# SmartON.net
KiCad netlist of a schematic drawn in EAGLE
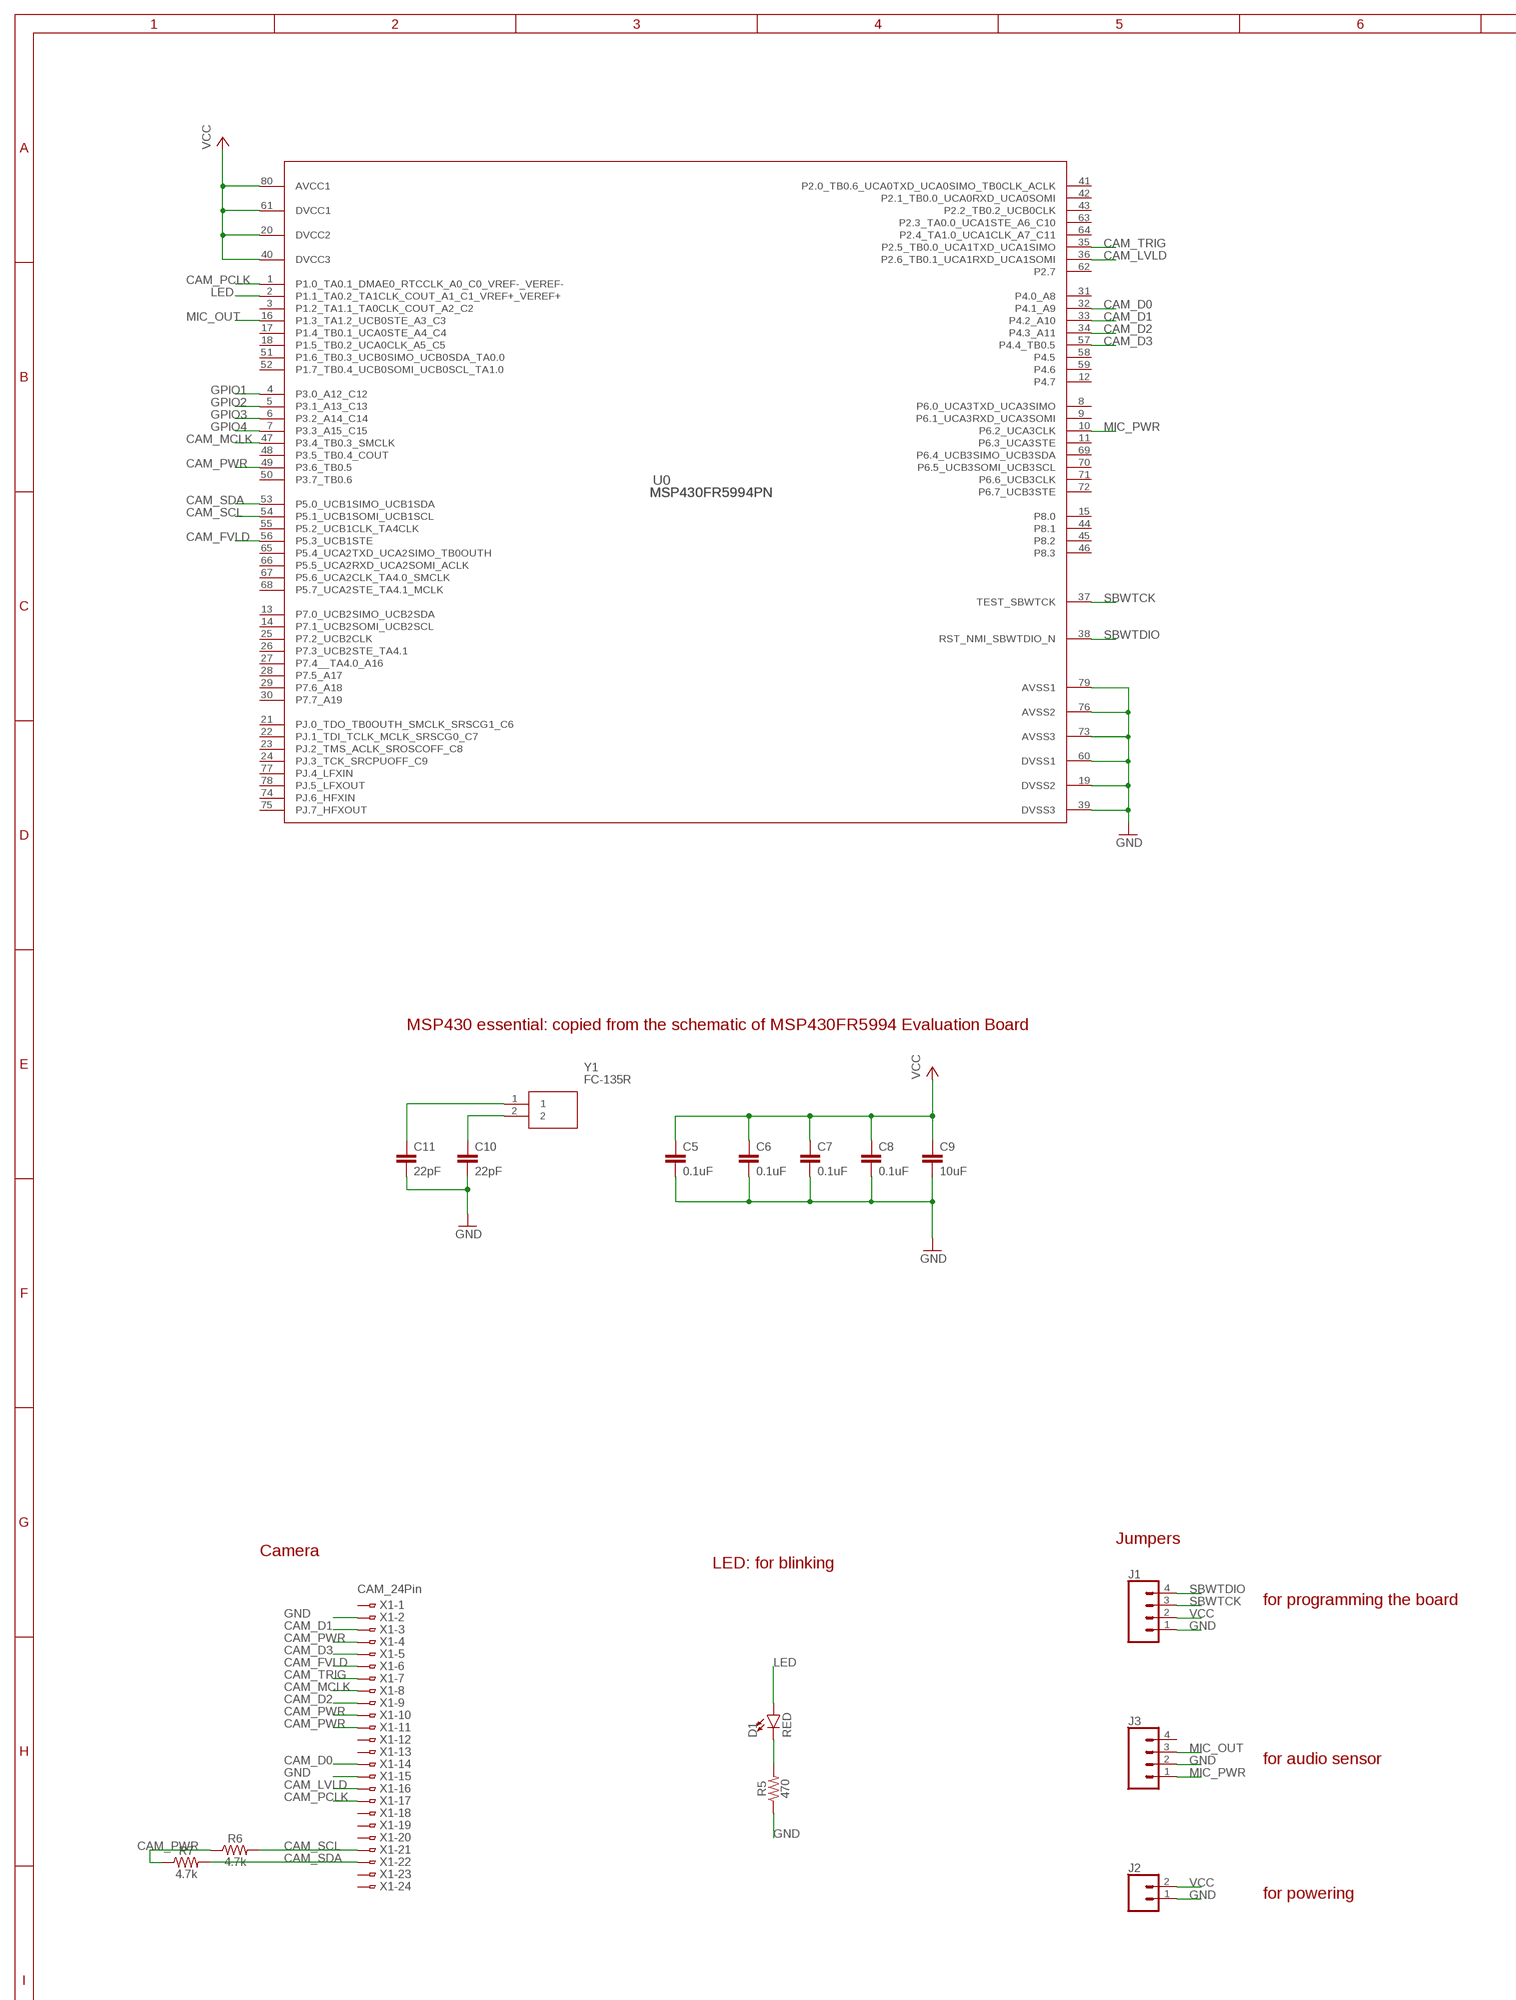
[diagram p0: schematic, sheet 1, part 1 of 2]
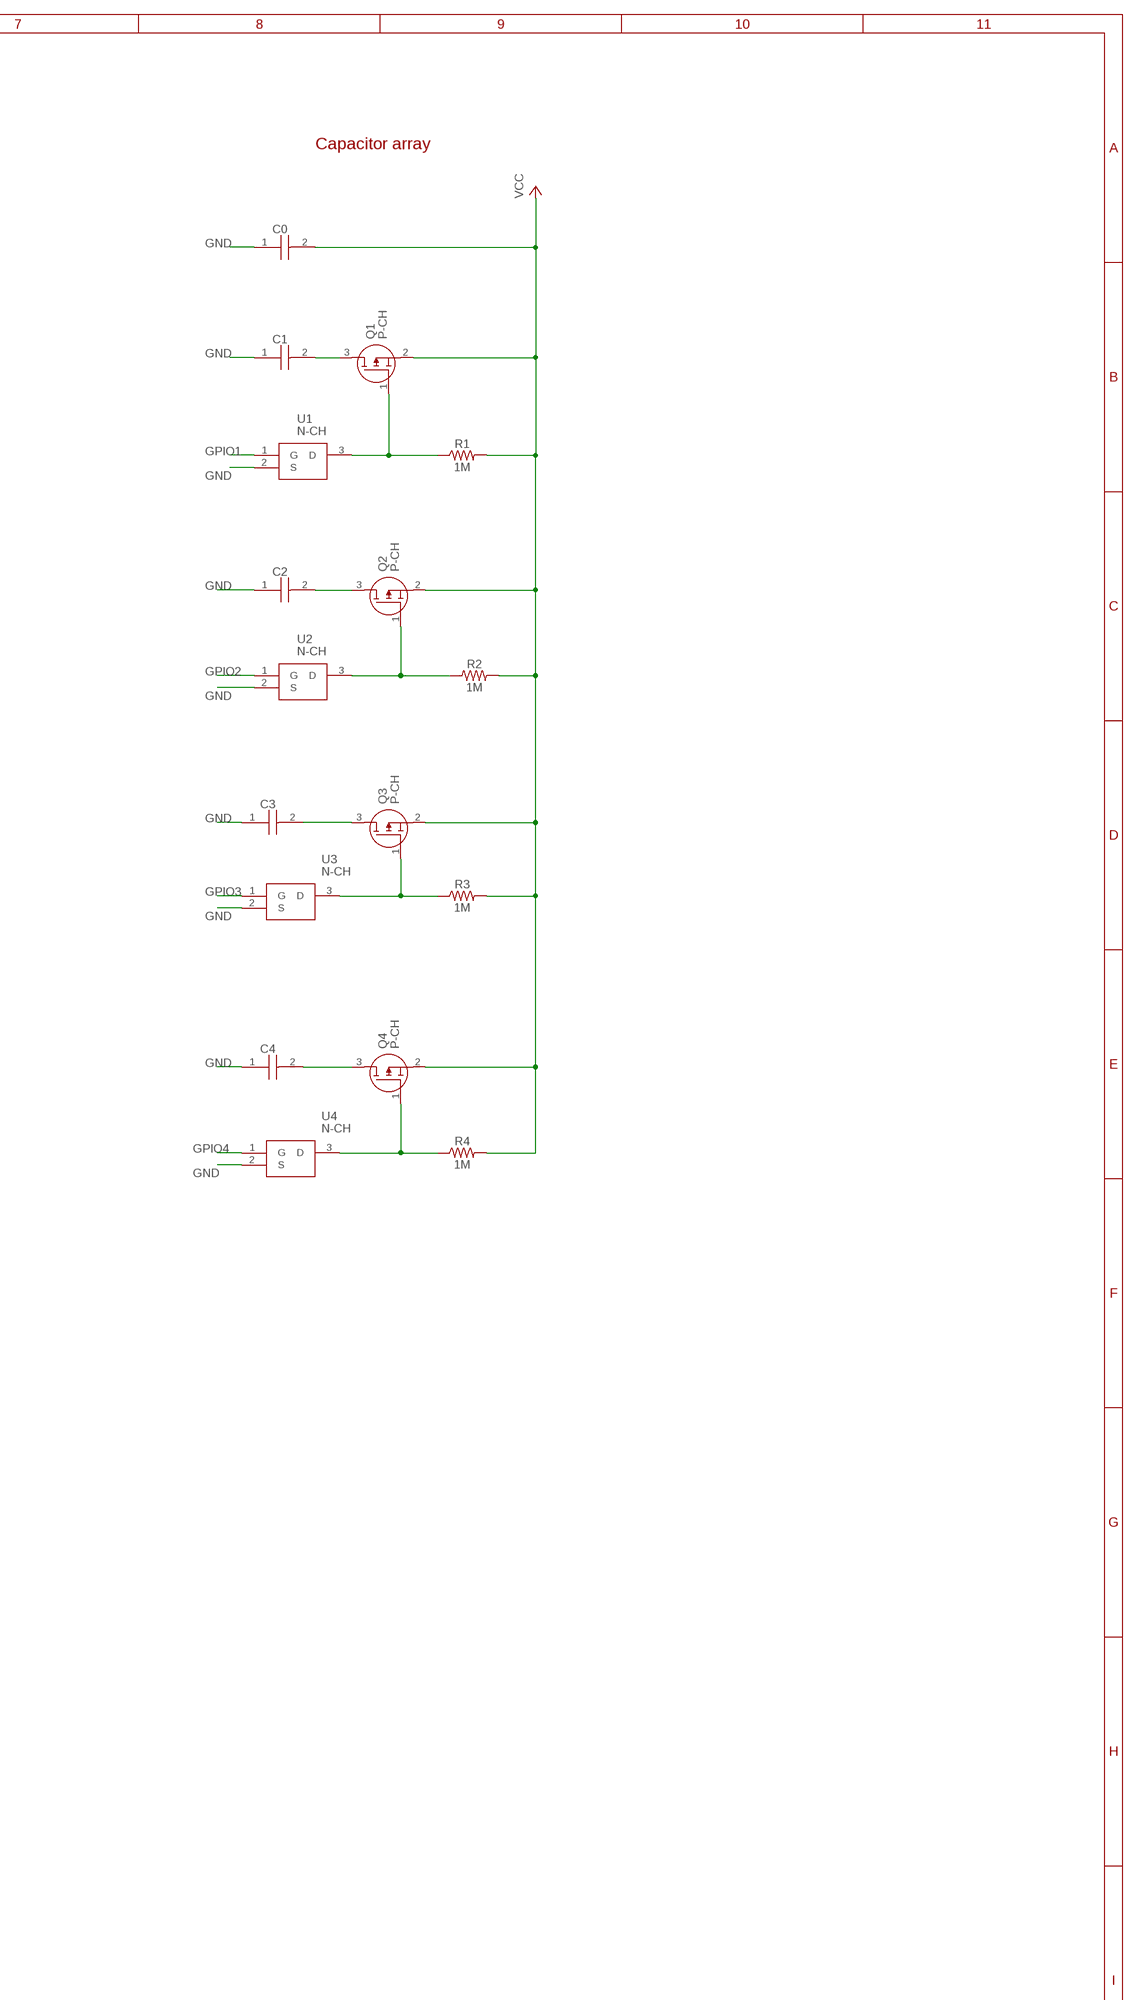
[diagram p1: schematic, sheet 1, part 2 of 2]

(export (version "E")
  (design (tool "Eeschema 10.0.6"))
  (components
    (comp (ref "C0")
      (value "DBN-5R5D224T")
      (footprint "eagle-import:CAPPRD500W130D1350H800")
      (libsource (lib "eagle-import") (part "DBN-5R5D224T"))
    )
    (comp (ref "C1")
      (value "DBN-5R5D224T")
      (footprint "eagle-import:CAPPRD500W130D1350H800")
      (libsource (lib "eagle-import") (part "DBN-5R5D224T"))
    )
    (comp (ref "C2")
      (value "DBN-5R5D224T")
      (footprint "eagle-import:CAPPRD500W130D1350H800")
      (libsource (lib "eagle-import") (part "DBN-5R5D224T"))
    )
    (comp (ref "C3")
      (value "DBN-5R5D224T")
      (footprint "eagle-import:CAPPRD500W130D1350H800")
      (libsource (lib "eagle-import") (part "DBN-5R5D224T"))
    )
    (comp (ref "C4")
      (value "DBN-5R5D224T")
      (footprint "eagle-import:CAPPRD500W130D1350H800")
      (libsource (lib "eagle-import") (part "DBN-5R5D224T"))
    )
    (comp (ref "C5")
      (value "0.1uF")
      (footprint "eagle-import:0603")
      (libsource (lib "eagle-import") (part "0.1UF-0603-25V-5%"))
    )
    (comp (ref "C6")
      (value "0.1uF")
      (footprint "eagle-import:0603")
      (libsource (lib "eagle-import") (part "0.1UF-0603-25V-5%"))
    )
    (comp (ref "C7")
      (value "0.1uF")
      (footprint "eagle-import:0603")
      (libsource (lib "eagle-import") (part "0.1UF-0603-25V-5%"))
    )
    (comp (ref "C8")
      (value "0.1uF")
      (footprint "eagle-import:0603")
      (libsource (lib "eagle-import") (part "0.1UF-0603-25V-5%"))
    )
    (comp (ref "C9")
      (value "10uF")
      (footprint "eagle-import:0603")
      (libsource (lib "eagle-import") (part "10UF-0603-6.3V-20%"))
    )
    (comp (ref "C10")
      (value "22pF")
      (footprint "eagle-import:0603")
      (libsource (lib "eagle-import") (part "22PF-0603-50V-5%"))
    )
    (comp (ref "C11")
      (value "22pF")
      (footprint "eagle-import:0603")
      (libsource (lib "eagle-import") (part "22PF-0603-50V-5%"))
    )
    (comp (ref "D1")
      (value "RED")
      (footprint "eagle-import:LED-0603")
      (libsource (lib "eagle-import") (part "LED-RED0603"))
    )
    (comp (ref "J1")
      (value "CONN_04LOCK")
      (footprint "eagle-import:1X04_LOCK")
      (libsource (lib "eagle-import") (part "CONN_04LOCK"))
    )
    (comp (ref "J2")
      (value "CONN_02")
      (footprint "eagle-import:1X02")
      (libsource (lib "eagle-import") (part "CONN_02"))
    )
    (comp (ref "J3")
      (value "CONN_04LOCK")
      (footprint "eagle-import:1X04_LOCK")
      (libsource (lib "eagle-import") (part "CONN_04LOCK"))
    )
    (comp (ref "Q1")
      (value "P-CH")
      (footprint "eagle-import:SOT95P237X112-3N")
      (fields (field (name "MANUFACTURER_PART_NUMBER") "IRLML5103PBF"))
      (libsource (lib "eagle-import") (part "IRLML5103PBF"))
    )
    (comp (ref "Q2")
      (value "P-CH")
      (footprint "eagle-import:SOT95P237X112-3N")
      (fields (field (name "MANUFACTURER_PART_NUMBER") "IRLML5103PBF"))
      (libsource (lib "eagle-import") (part "IRLML5103PBF"))
    )
    (comp (ref "Q3")
      (value "P-CH")
      (footprint "eagle-import:SOT95P237X112-3N")
      (fields (field (name "MANUFACTURER_PART_NUMBER") "IRLML5103PBF"))
      (libsource (lib "eagle-import") (part "IRLML5103PBF"))
    )
    (comp (ref "Q4")
      (value "P-CH")
      (footprint "eagle-import:SOT95P237X112-3N")
      (fields (field (name "MANUFACTURER_PART_NUMBER") "IRLML5103PBF"))
      (libsource (lib "eagle-import") (part "IRLML5103PBF"))
    )
    (comp (ref "R1")
      (value "1M")
      (footprint "eagle-import:0603")
      (libsource (lib "eagle-import") (part "1MOHM-0603-1/4W-5%"))
    )
    (comp (ref "R2")
      (value "1M")
      (footprint "eagle-import:0603")
      (libsource (lib "eagle-import") (part "1MOHM-0603-1/4W-5%"))
    )
    (comp (ref "R3")
      (value "1M")
      (footprint "eagle-import:0603")
      (libsource (lib "eagle-import") (part "1MOHM-0603-1/4W-5%"))
    )
    (comp (ref "R4")
      (value "1M")
      (footprint "eagle-import:0603")
      (libsource (lib "eagle-import") (part "1MOHM-0603-1/4W-5%"))
    )
    (comp (ref "R5")
      (value "470")
      (footprint "eagle-import:0603")
      (libsource (lib "eagle-import") (part "470OHM-0603-1/10W-1%"))
    )
    (comp (ref "R6")
      (value "4.7k")
      (footprint "eagle-import:0603")
      (libsource (lib "eagle-import") (part "4.7KOHM-0603-1/10W-1%"))
    )
    (comp (ref "R7")
      (value "4.7k")
      (footprint "eagle-import:0603")
      (libsource (lib "eagle-import") (part "4.7KOHM-0603-1/10W-1%"))
    )
    (comp (ref "U0")
      (value "MSP430FR5994PN")
      (footprint "eagle-import:PN0080A_N")
      (fields
        (field (name "MANUFACTURER") "Texas Instruments")
        (field (name "PARTNUMBER") "MSP430FR5994IPNR")
      )
      (libsource (lib "eagle-import") (part "MSP430FR5994IPN"))
    )
    (comp (ref "U1")
      (value "N-CH")
      (footprint "eagle-import:SOT95P240X110-3N")
      (fields
        (field (name "MANUFACTURER_PART_NUMBER") "DMN2004K-7")
        (field (name "MOUSER_PART_NUMBER") "621-DMN2004K-7")
        (field (name "RS_PART_NUMBER") "7082425P")
      )
      (libsource (lib "eagle-import") (part "DMN2004K-7"))
    )
    (comp (ref "U2")
      (value "N-CH")
      (footprint "eagle-import:SOT95P240X110-3N")
      (fields
        (field (name "MANUFACTURER_PART_NUMBER") "DMN2004K-7")
        (field (name "MOUSER_PART_NUMBER") "621-DMN2004K-7")
        (field (name "RS_PART_NUMBER") "7082425P")
      )
      (libsource (lib "eagle-import") (part "DMN2004K-7"))
    )
    (comp (ref "U3")
      (value "N-CH")
      (footprint "eagle-import:SOT95P240X110-3N")
      (fields
        (field (name "MANUFACTURER_PART_NUMBER") "DMN2004K-7")
        (field (name "MOUSER_PART_NUMBER") "621-DMN2004K-7")
        (field (name "RS_PART_NUMBER") "7082425P")
      )
      (libsource (lib "eagle-import") (part "DMN2004K-7"))
    )
    (comp (ref "U4")
      (value "N-CH")
      (footprint "eagle-import:SOT95P240X110-3N")
      (fields
        (field (name "MANUFACTURER_PART_NUMBER") "DMN2004K-7")
        (field (name "MOUSER_PART_NUMBER") "621-DMN2004K-7")
        (field (name "RS_PART_NUMBER") "7082425P")
      )
      (libsource (lib "eagle-import") (part "DMN2004K-7"))
    )
    (comp (ref "X1")
      (value "CAM_24Pin")
      (footprint "eagle-import:FH12-24S-0.5SH")
      (fields (field (name "MPN") "FH12-24S-0.5SH(55)"))
      (libsource (lib "eagle-import") (part "FH12-24S-0.5SH"))
    )
    (comp (ref "Y1")
      (value "FC-135R")
      (footprint "eagle-import:FC135327680KAAG0")
      (libsource (lib "eagle-import") (part "FC-135R"))
    )
  )
  (nets
    (net (code "1") (name "/CAM_D0") (class "Default")
      (node (ref "U0") (pin "32") (pinfunction "P4.1_A9_32") (pintype "bidirectional"))
      (node (ref "X1") (pin "14") (pinfunction "1_14") (pintype "passive"))
    )
    (net (code "2") (name "/CAM_D1") (class "Default")
      (node (ref "U0") (pin "33") (pinfunction "P4.2_A10_33") (pintype "bidirectional"))
      (node (ref "X1") (pin "3") (pinfunction "1_3") (pintype "passive"))
    )
    (net (code "3") (name "/CAM_D2") (class "Default")
      (node (ref "U0") (pin "34") (pinfunction "P4.3_A11_34") (pintype "bidirectional"))
      (node (ref "X1") (pin "9") (pinfunction "1_9") (pintype "passive"))
    )
    (net (code "4") (name "/CAM_D3") (class "Default")
      (node (ref "U0") (pin "57") (pinfunction "P4.4_TB0.5_57") (pintype "bidirectional"))
      (node (ref "X1") (pin "5") (pinfunction "1_5") (pintype "passive"))
    )
    (net (code "5") (name "/CAM_FVLD") (class "Default")
      (node (ref "U0") (pin "56") (pinfunction "P5.3_UCB1STE_56") (pintype "bidirectional"))
      (node (ref "X1") (pin "6") (pinfunction "1_6") (pintype "passive"))
    )
    (net (code "6") (name "/CAM_LVLD") (class "Default")
      (node (ref "U0") (pin "36") (pinfunction "P2.6_TB0.1_UCA1RXD_UCA1SOMI_36") (pintype "bidirectional"))
      (node (ref "X1") (pin "16") (pinfunction "1_16") (pintype "passive"))
    )
    (net (code "7") (name "/CAM_MCLK") (class "Default")
      (node (ref "U0") (pin "47") (pinfunction "P3.4_TB0.3_SMCLK_47") (pintype "bidirectional"))
      (node (ref "X1") (pin "8") (pinfunction "1_8") (pintype "passive"))
    )
    (net (code "8") (name "/CAM_PCLK") (class "Default")
      (node (ref "U0") (pin "1") (pinfunction "P1.0_TA0.1_DMAE0_RTCCLK_A0_C0_VREF-_VEREF-_1") (pintype "bidirectional"))
      (node (ref "X1") (pin "17") (pinfunction "1_17") (pintype "passive"))
    )
    (net (code "9") (name "/CAM_PWR") (class "Default")
      (node (ref "R6") (pin "1") (pinfunction "1_1") (pintype "passive"))
      (node (ref "R7") (pin "1") (pinfunction "1_1") (pintype "passive"))
      (node (ref "U0") (pin "49") (pinfunction "P3.6_TB0.5_49") (pintype "bidirectional"))
      (node (ref "X1") (pin "10") (pinfunction "1_10") (pintype "passive"))
      (node (ref "X1") (pin "11") (pinfunction "1_11") (pintype "passive"))
      (node (ref "X1") (pin "4") (pinfunction "1_4") (pintype "passive"))
    )
    (net (code "10") (name "/CAM_SCL") (class "Default")
      (node (ref "R6") (pin "2") (pinfunction "2_2") (pintype "passive"))
      (node (ref "U0") (pin "54") (pinfunction "P5.1_UCB1SOMI_UCB1SCL_54") (pintype "bidirectional"))
      (node (ref "X1") (pin "21") (pinfunction "1_21") (pintype "passive"))
    )
    (net (code "11") (name "/CAM_SDA") (class "Default")
      (node (ref "R7") (pin "2") (pinfunction "2_2") (pintype "passive"))
      (node (ref "U0") (pin "53") (pinfunction "P5.0_UCB1SIMO_UCB1SDA_53") (pintype "bidirectional"))
      (node (ref "X1") (pin "22") (pinfunction "1_22") (pintype "passive"))
    )
    (net (code "12") (name "/CAM_TRIG") (class "Default")
      (node (ref "U0") (pin "35") (pinfunction "P2.5_TB0.0_UCA1TXD_UCA1SIMO_35") (pintype "bidirectional"))
      (node (ref "X1") (pin "7") (pinfunction "1_7") (pintype "passive"))
    )
    (net (code "13") (name "/GPIO1") (class "Default")
      (node (ref "U0") (pin "4") (pinfunction "P3.0_A12_C12_4") (pintype "bidirectional"))
      (node (ref "U1") (pin "1") (pinfunction "G_1") (pintype "bidirectional"))
    )
    (net (code "14") (name "/GPIO2") (class "Default")
      (node (ref "U0") (pin "5") (pinfunction "P3.1_A13_C13_5") (pintype "bidirectional"))
      (node (ref "U2") (pin "1") (pinfunction "G_1") (pintype "bidirectional"))
    )
    (net (code "15") (name "/GPIO3") (class "Default")
      (node (ref "U0") (pin "6") (pinfunction "P3.2_A14_C14_6") (pintype "bidirectional"))
      (node (ref "U3") (pin "1") (pinfunction "G_1") (pintype "bidirectional"))
    )
    (net (code "16") (name "/GPIO4") (class "Default")
      (node (ref "U0") (pin "7") (pinfunction "P3.3_A15_C15_7") (pintype "bidirectional"))
      (node (ref "U4") (pin "1") (pinfunction "G_1") (pintype "bidirectional"))
    )
    (net (code "17") (name "/LED") (class "Default")
      (node (ref "D1") (pin "A") (pinfunction "A_A") (pintype "passive"))
      (node (ref "U0") (pin "2") (pinfunction "P1.1_TA0.2_TA1CLK_COUT_A1_C1_VREF+_VEREF+_2") (pintype "bidirectional"))
    )
    (net (code "18") (name "/MIC_OUT") (class "Default")
      (node (ref "J3") (pin "3") (pinfunction "3_3") (pintype "passive"))
      (node (ref "U0") (pin "16") (pinfunction "P1.3_TA1.2_UCB0STE_A3_C3_16") (pintype "bidirectional"))
    )
    (net (code "19") (name "/MIC_PWR") (class "Default")
      (node (ref "J3") (pin "1") (pinfunction "1_1") (pintype "passive"))
      (node (ref "U0") (pin "10") (pinfunction "P6.2_UCA3CLK_10") (pintype "bidirectional"))
    )
    (net (code "20") (name "/SBWTCK") (class "Default")
      (node (ref "J1") (pin "3") (pinfunction "3_3") (pintype "passive"))
      (node (ref "U0") (pin "37") (pinfunction "TEST_SBWTCK_37") (pintype "input"))
    )
    (net (code "21") (name "/SBWTDIO") (class "Default")
      (node (ref "J1") (pin "4") (pinfunction "4_4") (pintype "passive"))
      (node (ref "U0") (pin "38") (pinfunction "RST_NMI_SBWTDIO_N_38") (pintype "bidirectional"))
    )
    (net (code "22") (name "GND") (class "Default")
      (node (ref "C0") (pin "1") (pinfunction "+_1") (pintype "bidirectional"))
      (node (ref "C1") (pin "1") (pinfunction "+_1") (pintype "bidirectional"))
      (node (ref "C10") (pin "2") (pinfunction "2_2") (pintype "passive"))
      (node (ref "C11") (pin "2") (pinfunction "2_2") (pintype "passive"))
      (node (ref "C2") (pin "1") (pinfunction "+_1") (pintype "bidirectional"))
      (node (ref "C3") (pin "1") (pinfunction "+_1") (pintype "bidirectional"))
      (node (ref "C4") (pin "1") (pinfunction "+_1") (pintype "bidirectional"))
      (node (ref "C5") (pin "2") (pinfunction "2_2") (pintype "passive"))
      (node (ref "C6") (pin "2") (pinfunction "2_2") (pintype "passive"))
      (node (ref "C7") (pin "2") (pinfunction "2_2") (pintype "passive"))
      (node (ref "C8") (pin "2") (pinfunction "2_2") (pintype "passive"))
      (node (ref "C9") (pin "2") (pinfunction "2_2") (pintype "passive"))
      (node (ref "J1") (pin "1") (pinfunction "1_1") (pintype "passive"))
      (node (ref "J2") (pin "1") (pinfunction "1_1") (pintype "passive"))
      (node (ref "J3") (pin "2") (pinfunction "2_2") (pintype "passive"))
      (node (ref "R5") (pin "1") (pinfunction "1_1") (pintype "passive"))
      (node (ref "U0") (pin "19") (pinfunction "DVSS2_19") (pintype "power_in"))
      (node (ref "U0") (pin "39") (pinfunction "DVSS3_39") (pintype "power_in"))
      (node (ref "U0") (pin "60") (pinfunction "DVSS1_60") (pintype "power_in"))
      (node (ref "U0") (pin "73") (pinfunction "AVSS3_73") (pintype "power_in"))
      (node (ref "U0") (pin "76") (pinfunction "AVSS2_76") (pintype "power_in"))
      (node (ref "U0") (pin "79") (pinfunction "AVSS1_79") (pintype "power_in"))
      (node (ref "U1") (pin "2") (pinfunction "S_2") (pintype "bidirectional"))
      (node (ref "U2") (pin "2") (pinfunction "S_2") (pintype "bidirectional"))
      (node (ref "U3") (pin "2") (pinfunction "S_2") (pintype "bidirectional"))
      (node (ref "U4") (pin "2") (pinfunction "S_2") (pintype "bidirectional"))
      (node (ref "X1") (pin "15") (pinfunction "1_15") (pintype "passive"))
      (node (ref "X1") (pin "2") (pinfunction "1_2") (pintype "passive"))
    )
    (net (code "23") (name "Net-(C1--)") (class "Default")
      (node (ref "C1") (pin "2") (pinfunction "-_2") (pintype "bidirectional"))
      (node (ref "Q1") (pin "3") (pinfunction "D_3") (pintype "bidirectional"))
    )
    (net (code "24") (name "Net-(C2--)") (class "Default")
      (node (ref "C2") (pin "2") (pinfunction "-_2") (pintype "bidirectional"))
      (node (ref "Q2") (pin "3") (pinfunction "D_3") (pintype "bidirectional"))
    )
    (net (code "25") (name "Net-(C3--)") (class "Default")
      (node (ref "C3") (pin "2") (pinfunction "-_2") (pintype "bidirectional"))
      (node (ref "Q3") (pin "3") (pinfunction "D_3") (pintype "bidirectional"))
    )
    (net (code "26") (name "Net-(C4--)") (class "Default")
      (node (ref "C4") (pin "2") (pinfunction "-_2") (pintype "bidirectional"))
      (node (ref "Q4") (pin "3") (pinfunction "D_3") (pintype "bidirectional"))
    )
    (net (code "27") (name "Net-(C10-Pad1)") (class "Default")
      (node (ref "C10") (pin "1") (pinfunction "1_1") (pintype "passive"))
      (node (ref "Y1") (pin "2") (pinfunction "2_2") (pintype "bidirectional"))
    )
    (net (code "28") (name "Net-(C11-Pad1)") (class "Default")
      (node (ref "C11") (pin "1") (pinfunction "1_1") (pintype "passive"))
      (node (ref "Y1") (pin "1") (pinfunction "1_1") (pintype "bidirectional"))
    )
    (net (code "29") (name "Net-(D1-PadC)") (class "Default")
      (node (ref "D1") (pin "C") (pinfunction "C_C") (pintype "passive"))
      (node (ref "R5") (pin "2") (pinfunction "2_2") (pintype "passive"))
    )
    (net (code "30") (name "Net-(Q1-G)") (class "Default")
      (node (ref "Q1") (pin "1") (pinfunction "G_1") (pintype "bidirectional"))
      (node (ref "R1") (pin "1") (pinfunction "1_1") (pintype "passive"))
      (node (ref "U1") (pin "3") (pinfunction "D_3") (pintype "bidirectional"))
    )
    (net (code "31") (name "Net-(Q2-G)") (class "Default")
      (node (ref "Q2") (pin "1") (pinfunction "G_1") (pintype "bidirectional"))
      (node (ref "R2") (pin "1") (pinfunction "1_1") (pintype "passive"))
      (node (ref "U2") (pin "3") (pinfunction "D_3") (pintype "bidirectional"))
    )
    (net (code "32") (name "Net-(Q3-G)") (class "Default")
      (node (ref "Q3") (pin "1") (pinfunction "G_1") (pintype "bidirectional"))
      (node (ref "R3") (pin "1") (pinfunction "1_1") (pintype "passive"))
      (node (ref "U3") (pin "3") (pinfunction "D_3") (pintype "bidirectional"))
    )
    (net (code "33") (name "Net-(Q4-G)") (class "Default")
      (node (ref "Q4") (pin "1") (pinfunction "G_1") (pintype "bidirectional"))
      (node (ref "R4") (pin "1") (pinfunction "1_1") (pintype "passive"))
      (node (ref "U4") (pin "3") (pinfunction "D_3") (pintype "bidirectional"))
    )
    (net (code "34") (name "VCC") (class "Default")
      (node (ref "C0") (pin "2") (pinfunction "-_2") (pintype "bidirectional"))
      (node (ref "C5") (pin "1") (pinfunction "1_1") (pintype "passive"))
      (node (ref "C6") (pin "1") (pinfunction "1_1") (pintype "passive"))
      (node (ref "C7") (pin "1") (pinfunction "1_1") (pintype "passive"))
      (node (ref "C8") (pin "1") (pinfunction "1_1") (pintype "passive"))
      (node (ref "C9") (pin "1") (pinfunction "1_1") (pintype "passive"))
      (node (ref "J1") (pin "2") (pinfunction "2_2") (pintype "passive"))
      (node (ref "J2") (pin "2") (pinfunction "2_2") (pintype "passive"))
      (node (ref "Q1") (pin "2") (pinfunction "S_2") (pintype "bidirectional"))
      (node (ref "Q2") (pin "2") (pinfunction "S_2") (pintype "bidirectional"))
      (node (ref "Q3") (pin "2") (pinfunction "S_2") (pintype "bidirectional"))
      (node (ref "Q4") (pin "2") (pinfunction "S_2") (pintype "bidirectional"))
      (node (ref "R1") (pin "2") (pinfunction "2_2") (pintype "passive"))
      (node (ref "R2") (pin "2") (pinfunction "2_2") (pintype "passive"))
      (node (ref "R3") (pin "2") (pinfunction "2_2") (pintype "passive"))
      (node (ref "R4") (pin "2") (pinfunction "2_2") (pintype "passive"))
      (node (ref "U0") (pin "20") (pinfunction "DVCC2_20") (pintype "power_in"))
      (node (ref "U0") (pin "40") (pinfunction "DVCC3_40") (pintype "power_in"))
      (node (ref "U0") (pin "61") (pinfunction "DVCC1_61") (pintype "power_in"))
      (node (ref "U0") (pin "80") (pinfunction "AVCC1_80") (pintype "power_in"))
    )
    (net (code "35") (name "unconnected-(J3-Pad4)") (class "Default")
      (node (ref "J3") (pin "4") (pinfunction "4_4") (pintype "passive"))
    )
    (net (code "36") (name "unconnected-(U0-P1.2_TA1.1_TA0CLK_COUT_A2_C2-Pad3)") (class "Default")
      (node (ref "U0") (pin "3") (pinfunction "P1.2_TA1.1_TA0CLK_COUT_A2_C2_3") (pintype "bidirectional"))
    )
    (net (code "37") (name "unconnected-(U0-P1.4_TB0.1_UCA0STE_A4_C4-Pad17)") (class "Default")
      (node (ref "U0") (pin "17") (pinfunction "P1.4_TB0.1_UCA0STE_A4_C4_17") (pintype "bidirectional"))
    )
    (net (code "38") (name "unconnected-(U0-P1.5_TB0.2_UCA0CLK_A5_C5-Pad18)") (class "Default")
      (node (ref "U0") (pin "18") (pinfunction "P1.5_TB0.2_UCA0CLK_A5_C5_18") (pintype "bidirectional"))
    )
    (net (code "39") (name "unconnected-(U0-P1.6_TB0.3_UCB0SIMO_UCB0SDA_TA0.0-Pad51)") (class "Default")
      (node (ref "U0") (pin "51") (pinfunction "P1.6_TB0.3_UCB0SIMO_UCB0SDA_TA0.0_51") (pintype "bidirectional"))
    )
    (net (code "40") (name "unconnected-(U0-P1.7_TB0.4_UCB0SOMI_UCB0SCL_TA1.0-Pad52)") (class "Default")
      (node (ref "U0") (pin "52") (pinfunction "P1.7_TB0.4_UCB0SOMI_UCB0SCL_TA1.0_52") (pintype "bidirectional"))
    )
    (net (code "41") (name "unconnected-(U0-P2.0_TB0.6_UCA0TXD_UCA0SIMO_TB0CLK_ACLK-Pad41)") (class "Default")
      (node (ref "U0") (pin "41") (pinfunction "P2.0_TB0.6_UCA0TXD_UCA0SIMO_TB0CLK_ACLK_41") (pintype "bidirectional"))
    )
    (net (code "42") (name "unconnected-(U0-P2.1_TB0.0_UCA0RXD_UCA0SOMI-Pad42)") (class "Default")
      (node (ref "U0") (pin "42") (pinfunction "P2.1_TB0.0_UCA0RXD_UCA0SOMI_42") (pintype "bidirectional"))
    )
    (net (code "43") (name "unconnected-(U0-P2.2_TB0.2_UCB0CLK-Pad43)") (class "Default")
      (node (ref "U0") (pin "43") (pinfunction "P2.2_TB0.2_UCB0CLK_43") (pintype "bidirectional"))
    )
    (net (code "44") (name "unconnected-(U0-P2.3_TA0.0_UCA1STE_A6_C10-Pad63)") (class "Default")
      (node (ref "U0") (pin "63") (pinfunction "P2.3_TA0.0_UCA1STE_A6_C10_63") (pintype "bidirectional"))
    )
    (net (code "45") (name "unconnected-(U0-P2.4_TA1.0_UCA1CLK_A7_C11-Pad64)") (class "Default")
      (node (ref "U0") (pin "64") (pinfunction "P2.4_TA1.0_UCA1CLK_A7_C11_64") (pintype "bidirectional"))
    )
    (net (code "46") (name "unconnected-(U0-P2.7-Pad62)") (class "Default")
      (node (ref "U0") (pin "62") (pinfunction "P2.7_62") (pintype "bidirectional"))
    )
    (net (code "47") (name "unconnected-(U0-P3.5_TB0.4_COUT-Pad48)") (class "Default")
      (node (ref "U0") (pin "48") (pinfunction "P3.5_TB0.4_COUT_48") (pintype "bidirectional"))
    )
    (net (code "48") (name "unconnected-(U0-P3.7_TB0.6-Pad50)") (class "Default")
      (node (ref "U0") (pin "50") (pinfunction "P3.7_TB0.6_50") (pintype "bidirectional"))
    )
    (net (code "49") (name "unconnected-(U0-P4.0_A8-Pad31)") (class "Default")
      (node (ref "U0") (pin "31") (pinfunction "P4.0_A8_31") (pintype "bidirectional"))
    )
    (net (code "50") (name "unconnected-(U0-P4.5-Pad58)") (class "Default")
      (node (ref "U0") (pin "58") (pinfunction "P4.5_58") (pintype "bidirectional"))
    )
    (net (code "51") (name "unconnected-(U0-P4.6-Pad59)") (class "Default")
      (node (ref "U0") (pin "59") (pinfunction "P4.6_59") (pintype "bidirectional"))
    )
    (net (code "52") (name "unconnected-(U0-P4.7-Pad12)") (class "Default")
      (node (ref "U0") (pin "12") (pinfunction "P4.7_12") (pintype "bidirectional"))
    )
    (net (code "53") (name "unconnected-(U0-P5.2_UCB1CLK_TA4CLK-Pad55)") (class "Default")
      (node (ref "U0") (pin "55") (pinfunction "P5.2_UCB1CLK_TA4CLK_55") (pintype "bidirectional"))
    )
    (net (code "54") (name "unconnected-(U0-P5.4_UCA2TXD_UCA2SIMO_TB0OUTH-Pad65)") (class "Default")
      (node (ref "U0") (pin "65") (pinfunction "P5.4_UCA2TXD_UCA2SIMO_TB0OUTH_65") (pintype "bidirectional"))
    )
    (net (code "55") (name "unconnected-(U0-P5.5_UCA2RXD_UCA2SOMI_ACLK-Pad66)") (class "Default")
      (node (ref "U0") (pin "66") (pinfunction "P5.5_UCA2RXD_UCA2SOMI_ACLK_66") (pintype "bidirectional"))
    )
    (net (code "56") (name "unconnected-(U0-P5.6_UCA2CLK_TA4.0_SMCLK-Pad67)") (class "Default")
      (node (ref "U0") (pin "67") (pinfunction "P5.6_UCA2CLK_TA4.0_SMCLK_67") (pintype "bidirectional"))
    )
    (net (code "57") (name "unconnected-(U0-P5.7_UCA2STE_TA4.1_MCLK-Pad68)") (class "Default")
      (node (ref "U0") (pin "68") (pinfunction "P5.7_UCA2STE_TA4.1_MCLK_68") (pintype "bidirectional"))
    )
    (net (code "58") (name "unconnected-(U0-P6.0_UCA3TXD_UCA3SIMO-Pad8)") (class "Default")
      (node (ref "U0") (pin "8") (pinfunction "P6.0_UCA3TXD_UCA3SIMO_8") (pintype "bidirectional"))
    )
    (net (code "59") (name "unconnected-(U0-P6.1_UCA3RXD_UCA3SOMI-Pad9)") (class "Default")
      (node (ref "U0") (pin "9") (pinfunction "P6.1_UCA3RXD_UCA3SOMI_9") (pintype "bidirectional"))
    )
    (net (code "60") (name "unconnected-(U0-P6.3_UCA3STE-Pad11)") (class "Default")
      (node (ref "U0") (pin "11") (pinfunction "P6.3_UCA3STE_11") (pintype "bidirectional"))
    )
    (net (code "61") (name "unconnected-(U0-P6.4_UCB3SIMO_UCB3SDA-Pad69)") (class "Default")
      (node (ref "U0") (pin "69") (pinfunction "P6.4_UCB3SIMO_UCB3SDA_69") (pintype "bidirectional"))
    )
    (net (code "62") (name "unconnected-(U0-P6.5_UCB3SOMI_UCB3SCL-Pad70)") (class "Default")
      (node (ref "U0") (pin "70") (pinfunction "P6.5_UCB3SOMI_UCB3SCL_70") (pintype "bidirectional"))
    )
    (net (code "63") (name "unconnected-(U0-P6.6_UCB3CLK-Pad71)") (class "Default")
      (node (ref "U0") (pin "71") (pinfunction "P6.6_UCB3CLK_71") (pintype "bidirectional"))
    )
    (net (code "64") (name "unconnected-(U0-P6.7_UCB3STE-Pad72)") (class "Default")
      (node (ref "U0") (pin "72") (pinfunction "P6.7_UCB3STE_72") (pintype "bidirectional"))
    )
    (net (code "65") (name "unconnected-(U0-P7.0_UCB2SIMO_UCB2SDA-Pad13)") (class "Default")
      (node (ref "U0") (pin "13") (pinfunction "P7.0_UCB2SIMO_UCB2SDA_13") (pintype "bidirectional"))
    )
    (net (code "66") (name "unconnected-(U0-P7.1_UCB2SOMI_UCB2SCL-Pad14)") (class "Default")
      (node (ref "U0") (pin "14") (pinfunction "P7.1_UCB2SOMI_UCB2SCL_14") (pintype "bidirectional"))
    )
    (net (code "67") (name "unconnected-(U0-P7.2_UCB2CLK-Pad25)") (class "Default")
      (node (ref "U0") (pin "25") (pinfunction "P7.2_UCB2CLK_25") (pintype "bidirectional"))
    )
    (net (code "68") (name "unconnected-(U0-P7.3_UCB2STE_TA4.1-Pad26)") (class "Default")
      (node (ref "U0") (pin "26") (pinfunction "P7.3_UCB2STE_TA4.1_26") (pintype "bidirectional"))
    )
    (net (code "69") (name "unconnected-(U0-P7.4__TA4.0_A16-Pad27)") (class "Default")
      (node (ref "U0") (pin "27") (pinfunction "P7.4__TA4.0_A16_27") (pintype "bidirectional"))
    )
    (net (code "70") (name "unconnected-(U0-P7.5_A17-Pad28)") (class "Default")
      (node (ref "U0") (pin "28") (pinfunction "P7.5_A17_28") (pintype "bidirectional"))
    )
    (net (code "71") (name "unconnected-(U0-P7.6_A18-Pad29)") (class "Default")
      (node (ref "U0") (pin "29") (pinfunction "P7.6_A18_29") (pintype "bidirectional"))
    )
    (net (code "72") (name "unconnected-(U0-P7.7_A19-Pad30)") (class "Default")
      (node (ref "U0") (pin "30") (pinfunction "P7.7_A19_30") (pintype "bidirectional"))
    )
    (net (code "73") (name "unconnected-(U0-P8.0-Pad15)") (class "Default")
      (node (ref "U0") (pin "15") (pinfunction "P8.0_15") (pintype "bidirectional"))
    )
    (net (code "74") (name "unconnected-(U0-P8.1-Pad44)") (class "Default")
      (node (ref "U0") (pin "44") (pinfunction "P8.1_44") (pintype "bidirectional"))
    )
    (net (code "75") (name "unconnected-(U0-P8.2-Pad45)") (class "Default")
      (node (ref "U0") (pin "45") (pinfunction "P8.2_45") (pintype "bidirectional"))
    )
    (net (code "76") (name "unconnected-(U0-P8.3-Pad46)") (class "Default")
      (node (ref "U0") (pin "46") (pinfunction "P8.3_46") (pintype "bidirectional"))
    )
    (net (code "77") (name "unconnected-(U0-PJ.0_TDO_TB0OUTH_SMCLK_SRSCG1_C6-Pad21)") (class "Default")
      (node (ref "U0") (pin "21") (pinfunction "PJ.0_TDO_TB0OUTH_SMCLK_SRSCG1_C6_21") (pintype "bidirectional"))
    )
    (net (code "78") (name "unconnected-(U0-PJ.1_TDI_TCLK_MCLK_SRSCG0_C7-Pad22)") (class "Default")
      (node (ref "U0") (pin "22") (pinfunction "PJ.1_TDI_TCLK_MCLK_SRSCG0_C7_22") (pintype "bidirectional"))
    )
    (net (code "79") (name "unconnected-(U0-PJ.2_TMS_ACLK_SROSCOFF_C8-Pad23)") (class "Default")
      (node (ref "U0") (pin "23") (pinfunction "PJ.2_TMS_ACLK_SROSCOFF_C8_23") (pintype "bidirectional"))
    )
    (net (code "80") (name "unconnected-(U0-PJ.3_TCK_SRCPUOFF_C9-Pad24)") (class "Default")
      (node (ref "U0") (pin "24") (pinfunction "PJ.3_TCK_SRCPUOFF_C9_24") (pintype "bidirectional"))
    )
    (net (code "81") (name "unconnected-(U0-PJ.4_LFXIN-Pad77)") (class "Default")
      (node (ref "U0") (pin "77") (pinfunction "PJ.4_LFXIN_77") (pintype "bidirectional"))
    )
    (net (code "82") (name "unconnected-(U0-PJ.5_LFXOUT-Pad78)") (class "Default")
      (node (ref "U0") (pin "78") (pinfunction "PJ.5_LFXOUT_78") (pintype "bidirectional"))
    )
    (net (code "83") (name "unconnected-(U0-PJ.6_HFXIN-Pad74)") (class "Default")
      (node (ref "U0") (pin "74") (pinfunction "PJ.6_HFXIN_74") (pintype "bidirectional"))
    )
    (net (code "84") (name "unconnected-(U0-PJ.7_HFXOUT-Pad75)") (class "Default")
      (node (ref "U0") (pin "75") (pinfunction "PJ.7_HFXOUT_75") (pintype "bidirectional"))
    )
    (net (code "85") (name "unconnected-(X1-Pad1)") (class "Default")
      (node (ref "X1") (pin "1") (pinfunction "1_1") (pintype "passive"))
    )
    (net (code "86") (name "unconnected-(X1D-1-Pad12)") (class "Default")
      (node (ref "X1") (pin "12") (pinfunction "1_12") (pintype "passive"))
    )
    (net (code "87") (name "unconnected-(X1E-1-Pad13)") (class "Default")
      (node (ref "X1") (pin "13") (pinfunction "1_13") (pintype "passive"))
    )
    (net (code "88") (name "unconnected-(X1J-1-Pad18)") (class "Default")
      (node (ref "X1") (pin "18") (pinfunction "1_18") (pintype "passive"))
    )
    (net (code "89") (name "unconnected-(X1K-1-Pad19)") (class "Default")
      (node (ref "X1") (pin "19") (pinfunction "1_19") (pintype "passive"))
    )
    (net (code "90") (name "unconnected-(X1M-1-Pad20)") (class "Default")
      (node (ref "X1") (pin "20") (pinfunction "1_20") (pintype "passive"))
    )
    (net (code "91") (name "unconnected-(X1P-1-Pad23)") (class "Default")
      (node (ref "X1") (pin "23") (pinfunction "1_23") (pintype "passive"))
    )
    (net (code "92") (name "unconnected-(X1Q-1-Pad24)") (class "Default")
      (node (ref "X1") (pin "24") (pinfunction "1_24") (pintype "passive"))
    )
  )
)
